# output_jack.net
KiCad netlist of a schematic drawn in Altium Designer
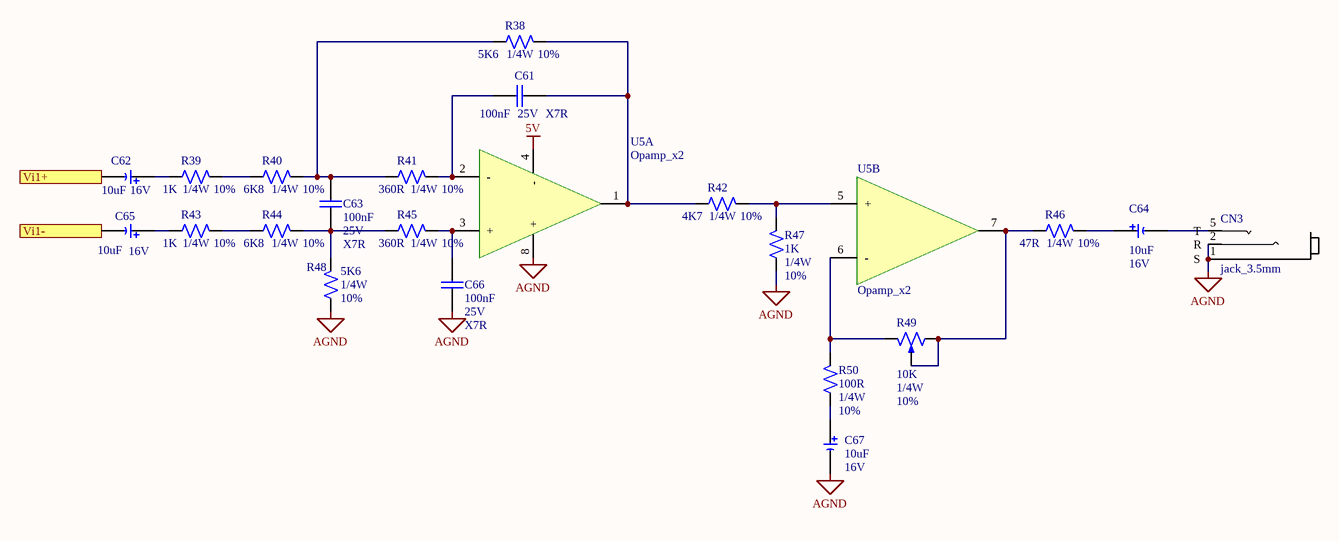
[diagram p0: output_jack.SchDoc]

(export (version "E")
  (design (tool "Eeschema 10.0.6"))
  (components
    (comp (ref "C61")
      (value "Capacitor")
      (footprint "C0805")
      (description "Capacitor de placas paralelas")
      (fields (field (name "VALOR") "100nF") (field (name "TENSION") "25V") (field (name "TOLERANCIA") "X7R"))
      (libsource (lib "Sch_Comunes") (part "Capacitor"))
    )
    (comp (ref "C62")
      (value "Capacitor polarizado")
      (footprint "CAP_Electrolytic")
      (fields (field (name "VALOR") "10uF") (field (name "TENSION") "16V"))
      (libsource (lib "Sch_Comunes") (part "Capacitor polarizado"))
    )
    (comp (ref "C63")
      (value "Capacitor")
      (footprint "C0805")
      (description "Capacitor de placas paralelas")
      (fields (field (name "VALOR") "100nF") (field (name "TENSION") "25V") (field (name "TOLERANCIA") "X7R"))
      (libsource (lib "Sch_Comunes") (part "Capacitor"))
    )
    (comp (ref "C64")
      (value "Capacitor polarizado")
      (footprint "CAP_Electrolytic")
      (fields (field (name "VALOR") "10uF") (field (name "TENSION") "16V"))
      (libsource (lib "Sch_Comunes") (part "Capacitor polarizado"))
    )
    (comp (ref "C65")
      (value "Capacitor polarizado")
      (footprint "CAP_Electrolytic")
      (fields (field (name "VALOR") "10uF") (field (name "TENSION") "16V"))
      (libsource (lib "Sch_Comunes") (part "Capacitor polarizado"))
    )
    (comp (ref "C66")
      (value "Capacitor")
      (footprint "C0805")
      (description "Capacitor de placas paralelas")
      (fields (field (name "VALOR") "100nF") (field (name "TENSION") "25V") (field (name "TOLERANCIA") "X7R"))
      (libsource (lib "Sch_Comunes") (part "Capacitor"))
    )
    (comp (ref "C67")
      (value "Capacitor polarizado")
      (footprint "CAP_Electrolytic")
      (fields (field (name "VALOR") "10uF") (field (name "TENSION") "16V"))
      (libsource (lib "") (part "Capacitor polarizado_1"))
    )
    (comp (ref "CN3")
      (value "jack_3.5mm")
      (footprint "Jack 3.5mm")
      (libsource (lib "Sch_Conectores") (part "jack_3.5mm"))
    )
    (comp (ref "R38")
      (value "Resistor")
      (footprint "R0805")
      (description "Resistencia")
      (fields (field (name "VALOR") "5K6") (field (name "POTENCIA") "1/4W") (field (name "TOLERANCIA") "10%"))
      (libsource (lib "sch_comunes") (part "Resistor"))
    )
    (comp (ref "R39")
      (value "Resistor")
      (footprint "R0805")
      (description "Resistencia")
      (fields (field (name "VALOR") "1K") (field (name "POTENCIA") "1/4W") (field (name "TOLERANCIA") "10%"))
      (libsource (lib "sch_comunes") (part "Resistor"))
    )
    (comp (ref "R40")
      (value "Resistor")
      (footprint "R0805")
      (description "Resistencia")
      (fields (field (name "VALOR") "6K8") (field (name "POTENCIA") "1/4W") (field (name "TOLERANCIA") "10%"))
      (libsource (lib "sch_comunes") (part "Resistor"))
    )
    (comp (ref "R41")
      (value "Resistor")
      (footprint "R0805")
      (description "Resistencia")
      (fields
        (field (name "VALOR") "360R")
        (field (name "POTENCIA") "1/4W")
        (field (name "TOLERANCIA") "10%")
      )
      (libsource (lib "sch_comunes") (part "Resistor"))
    )
    (comp (ref "R42")
      (value "Resistor")
      (footprint "R0805")
      (description "Resistencia")
      (fields (field (name "VALOR") "4K7") (field (name "POTENCIA") "1/4W") (field (name "TOLERANCIA") "10%"))
      (libsource (lib "sch_comunes") (part "Resistor"))
    )
    (comp (ref "R43")
      (value "Resistor")
      (footprint "R0805")
      (description "Resistencia")
      (fields (field (name "VALOR") "1K") (field (name "POTENCIA") "1/4W") (field (name "TOLERANCIA") "10%"))
      (libsource (lib "sch_comunes") (part "Resistor"))
    )
    (comp (ref "R44")
      (value "Resistor")
      (footprint "R0805")
      (description "Resistencia")
      (fields (field (name "VALOR") "6K8") (field (name "POTENCIA") "1/4W") (field (name "TOLERANCIA") "10%"))
      (libsource (lib "sch_comunes") (part "Resistor"))
    )
    (comp (ref "R45")
      (value "Resistor")
      (footprint "R0805")
      (description "Resistencia")
      (fields
        (field (name "VALOR") "360R")
        (field (name "POTENCIA") "1/4W")
        (field (name "TOLERANCIA") "10%")
      )
      (libsource (lib "sch_comunes") (part "Resistor"))
    )
    (comp (ref "R46")
      (value "Resistor")
      (footprint "R0805")
      (description "Resistencia")
      (fields (field (name "VALOR") "47R") (field (name "POTENCIA") "1/4W") (field (name "TOLERANCIA") "10%"))
      (libsource (lib "sch_comunes") (part "Resistor"))
    )
    (comp (ref "R47")
      (value "Resistor")
      (footprint "R0805")
      (description "Resistencia")
      (fields (field (name "VALOR") "1K") (field (name "POTENCIA") "1/4W") (field (name "TOLERANCIA") "10%"))
      (libsource (lib "sch_comunes") (part "Resistor"))
    )
    (comp (ref "R48")
      (value "Resistor")
      (footprint "R0805")
      (description "Resistencia")
      (fields (field (name "VALOR") "5K6") (field (name "POTENCIA") "1/4W") (field (name "TOLERANCIA") "10%"))
      (libsource (lib "sch_comunes") (part "Resistor"))
    )
    (comp (ref "R49")
      (value "Potenciometro")
      (footprint "Header 3x1")
      (fields (field (name "VALOR") "10K") (field (name "POTENCIA") "1/4W") (field (name "TOLERANCIA") "10%"))
      (libsource (lib "Sch_Comunes") (part "Potenciometer"))
    )
    (comp (ref "R50")
      (value "Resistor")
      (footprint "R0805")
      (description "Resistencia")
      (fields
        (field (name "VALOR") "100R")
        (field (name "POTENCIA") "1/4W")
        (field (name "TOLERANCIA") "10%")
      )
      (libsource (lib "sch_comunes") (part "Resistor"))
    )
    (comp (ref "U5")
      (value "Opamp_x2")
      (footprint "D8")
      (description "Integrado con 2 operacionales")
      (libsource (lib "sch_opamp") (part "Opamp_x2"))
    )
  )
  (nets
    (net (code "1") (name "/Vi1+") (class "Default")
      (node (ref "C62") (pin "2") (pinfunction "2_2") (pintype "passive"))
    )
    (net (code "2") (name "/Vi1-") (class "Default")
      (node (ref "C65") (pin "2") (pinfunction "2_2") (pintype "passive"))
    )
    (net (code "3") (name "5V") (class "Default")
      (node (ref "U5") (pin "4") (pinfunction "-_4") (pintype "passive"))
    )
    (net (code "4") (name "AGND") (class "Default")
      (node (ref "C66") (pin "2") (pinfunction "2_2") (pintype "passive"))
      (node (ref "C67") (pin "2") (pinfunction "2_2") (pintype "passive"))
      (node (ref "CN3") (pin "1") (pinfunction "S_1") (pintype "passive"))
      (node (ref "CN3") (pin "2") (pinfunction "R_2") (pintype "passive"))
      (node (ref "R47") (pin "1") (pinfunction "1_1") (pintype "passive"))
      (node (ref "R48") (pin "1") (pinfunction "1_1") (pintype "passive"))
      (node (ref "U5") (pin "8") (pinfunction "+_8") (pintype "power_in"))
    )
    (net (code "5") (name "Net-(C61-Pad2)") (class "Default")
      (node (ref "C61") (pin "2") (pinfunction "2_2") (pintype "passive"))
      (node (ref "R41") (pin "2") (pinfunction "2_2") (pintype "passive"))
      (node (ref "U5") (pin "2") (pinfunction "-_2") (pintype "passive"))
    )
    (net (code "6") (name "Net-(C62-Pad1)") (class "Default")
      (node (ref "C62") (pin "1") (pinfunction "1_1") (pintype "passive"))
      (node (ref "R39") (pin "1") (pinfunction "1_1") (pintype "passive"))
    )
    (net (code "7") (name "Net-(C63-Pad1)") (class "Default")
      (node (ref "C63") (pin "1") (pinfunction "1_1") (pintype "passive"))
      (node (ref "R38") (pin "1") (pinfunction "1_1") (pintype "passive"))
      (node (ref "R40") (pin "2") (pinfunction "2_2") (pintype "passive"))
      (node (ref "R41") (pin "1") (pinfunction "1_1") (pintype "passive"))
    )
    (net (code "8") (name "Net-(C63-Pad2)") (class "Default")
      (node (ref "C63") (pin "2") (pinfunction "2_2") (pintype "passive"))
      (node (ref "R44") (pin "2") (pinfunction "2_2") (pintype "passive"))
      (node (ref "R45") (pin "1") (pinfunction "1_1") (pintype "passive"))
      (node (ref "R48") (pin "2") (pinfunction "2_2") (pintype "passive"))
    )
    (net (code "9") (name "Net-(C64-Pad1)") (class "Default")
      (node (ref "C64") (pin "1") (pinfunction "1_1") (pintype "passive"))
      (node (ref "R46") (pin "2") (pinfunction "2_2") (pintype "passive"))
    )
    (net (code "10") (name "Net-(C65-Pad1)") (class "Default")
      (node (ref "C65") (pin "1") (pinfunction "1_1") (pintype "passive"))
      (node (ref "R43") (pin "1") (pinfunction "1_1") (pintype "passive"))
    )
    (net (code "11") (name "Net-(C66-Pad1)") (class "Default")
      (node (ref "C66") (pin "1") (pinfunction "1_1") (pintype "passive"))
      (node (ref "R45") (pin "2") (pinfunction "2_2") (pintype "passive"))
      (node (ref "U5") (pin "3") (pinfunction "+_3") (pintype "passive"))
    )
    (net (code "12") (name "Net-(C67-Pad1)") (class "Default")
      (node (ref "C67") (pin "1") (pinfunction "1_1") (pintype "passive"))
      (node (ref "R50") (pin "1") (pinfunction "1_1") (pintype "passive"))
    )
    (net (code "13") (name "Net-(CN3-T)") (class "Default")
      (node (ref "C64") (pin "2") (pinfunction "2_2") (pintype "passive"))
      (node (ref "CN3") (pin "5") (pinfunction "T_5") (pintype "passive"))
    )
    (net (code "14") (name "Net-(R39-Pad2)") (class "Default")
      (node (ref "R39") (pin "2") (pinfunction "2_2") (pintype "passive"))
      (node (ref "R40") (pin "1") (pinfunction "1_1") (pintype "passive"))
    )
    (net (code "15") (name "Net-(R43-Pad2)") (class "Default")
      (node (ref "R43") (pin "2") (pinfunction "2_2") (pintype "passive"))
      (node (ref "R44") (pin "1") (pinfunction "1_1") (pintype "passive"))
    )
    (net (code "16") (name "Net-(R49-Left)") (class "Default")
      (node (ref "R49") (pin "1") (pinfunction "Left_1") (pintype "passive"))
      (node (ref "R50") (pin "2") (pinfunction "2_2") (pintype "passive"))
      (node (ref "U5") (pin "6") (pinfunction "-_6") (pintype "passive"))
    )
    (net (code "17") (name "Net-(R49-Punto_medio)") (class "Default")
      (node (ref "R46") (pin "1") (pinfunction "1_1") (pintype "passive"))
      (node (ref "R49") (pin "2") (pinfunction "Punto_medio_2") (pintype "passive"))
      (node (ref "R49") (pin "3") (pinfunction "Right_3") (pintype "passive"))
      (node (ref "U5") (pin "7") (pinfunction "OUT_7") (pintype "passive"))
    )
    (net (code "18") (name "Net-(U5A-OUT)") (class "Default")
      (node (ref "C61") (pin "1") (pinfunction "1_1") (pintype "passive"))
      (node (ref "R38") (pin "2") (pinfunction "2_2") (pintype "passive"))
      (node (ref "R42") (pin "1") (pinfunction "1_1") (pintype "passive"))
      (node (ref "U5") (pin "1") (pinfunction "OUT_1") (pintype "passive"))
    )
    (net (code "19") (name "Net-(U5B-+)") (class "Default")
      (node (ref "R42") (pin "2") (pinfunction "2_2") (pintype "passive"))
      (node (ref "R47") (pin "2") (pinfunction "2_2") (pintype "passive"))
      (node (ref "U5") (pin "5") (pinfunction "+_5") (pintype "passive"))
    )
  )
)
